# pt100.net
KiCad netlist of a schematic drawn in Altium Designer
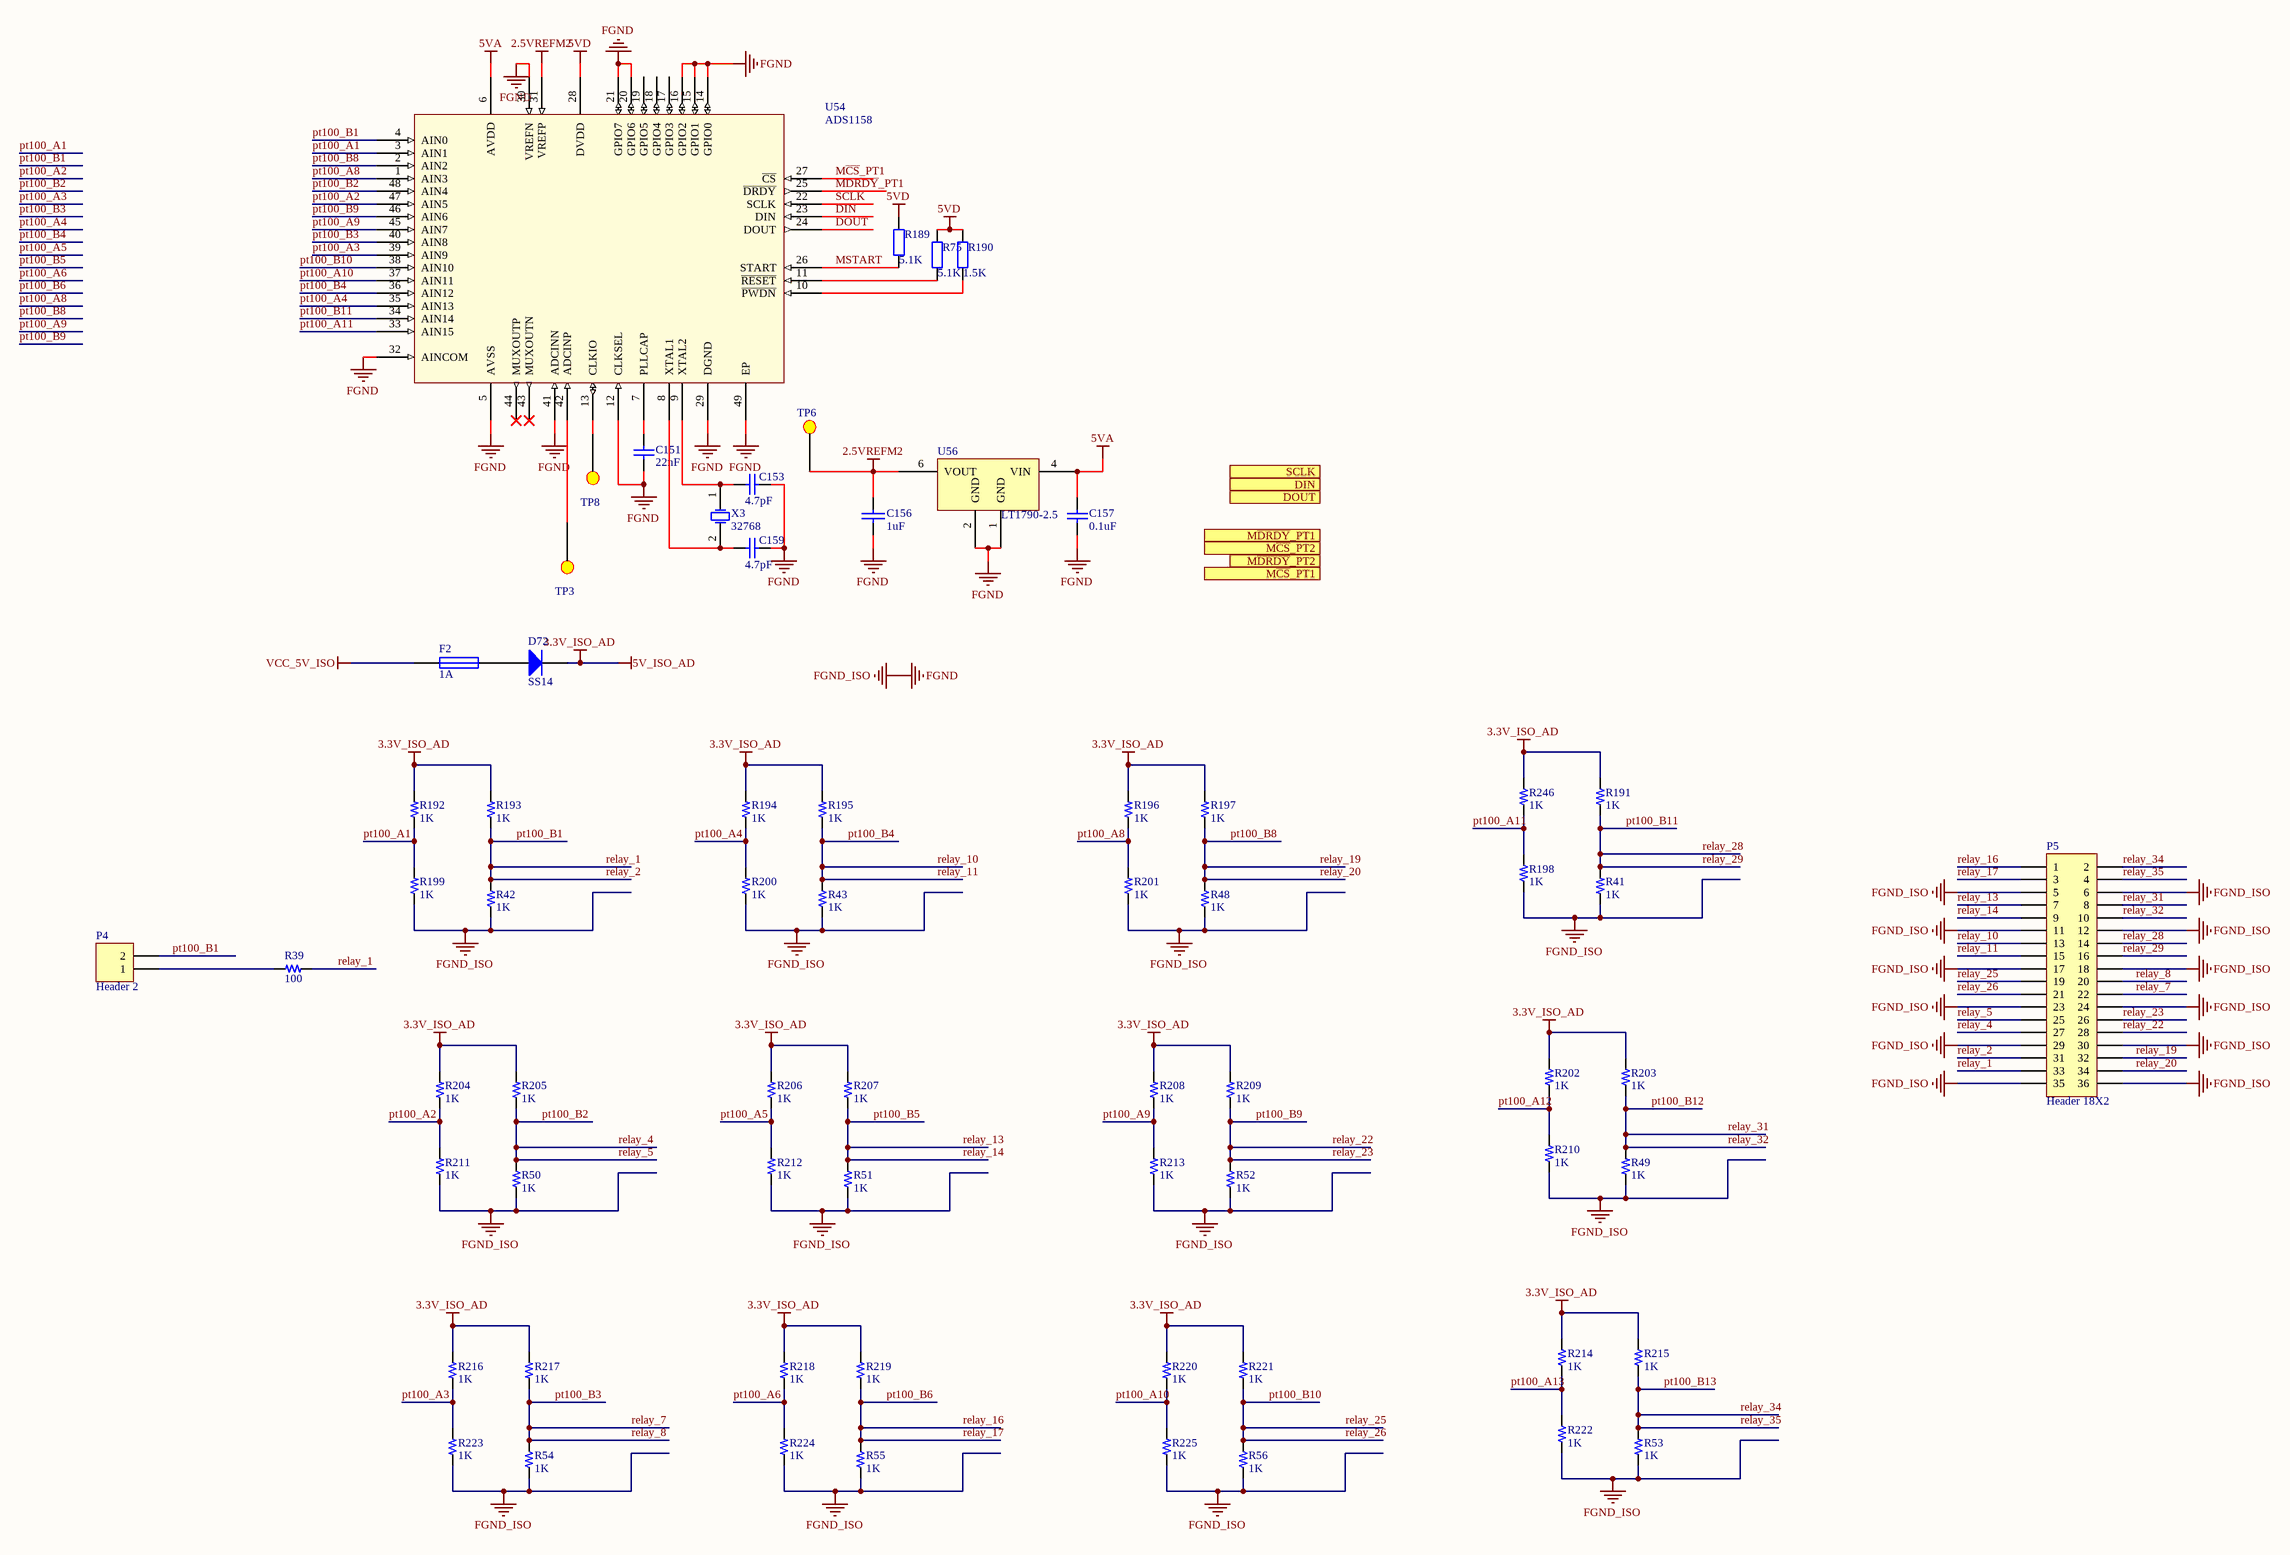
[diagram p0: pt100.SchDoc]

(export (version "E")
  (design (tool "Eeschema 10.0.6"))
  (components
    (comp (ref "C151")
      (value "22nF")
      (footprint "0805C")
      (description "Capacitor")
      (fields (field (name "PUBLISHER") "Altium Limited"))
      (libsource (lib "Miscellaneous Devices") (part "Cap"))
    )
    (comp (ref "C153")
      (value "4.7pF")
      (footprint "0603C")
      (description "Capacitor")
      (fields (field (name "PUBLISHER") "Altium Limited"))
      (libsource (lib "Miscellaneous Devices") (part "Cap"))
    )
    (comp (ref "C156")
      (value "1uF")
      (footprint "0603C")
      (description "Capacitor")
      (libsource (lib "*") (part "CAP"))
    )
    (comp (ref "C157")
      (value "0.1uF")
      (footprint "0603C")
      (description "Capacitor")
      (fields (field (name "PUBLISHER") "Altium Limited"))
      (libsource (lib "Miscellaneous Devices") (part "Cap"))
    )
    (comp (ref "C159")
      (value "4.7pF")
      (footprint "0603C")
      (description "Capacitor")
      (fields (field (name "PUBLISHER") "Altium Limited"))
      (libsource (lib "Miscellaneous Devices") (part "Cap"))
    )
    (comp (ref "D72")
      (value "SS14")
      (footprint "DO-214AC")
      (description "Default Diode")
      (fields (field (name "PUBLISHER") "Altium Limited"))
      (libsource (lib "Miscellaneous Devices") (part "Diode"))
    )
    (comp (ref "F2")
      (value "1A")
      (footprint "0805r")
      (description "Fuse")
      (fields (field (name "PUBLISHER") "Altium Limited"))
      (libsource (lib "Miscellaneous Devices") (part "Fuse 1"))
    )
    (comp (ref "P4")
      (value "Header 2")
      (footprint "HDR1X2")
      (description "Header, 2-Pin")
      (fields (field (name "PUBLISHER") "Altium Limited"))
      (libsource (lib "Miscellaneous Connectors") (part "Header 2"))
    )
    (comp (ref "P5")
      (value "Header 18X2")
      (footprint "XH2.54_2x18")
      (description "Header, 18-Pin, Dual row")
      (fields (field (name "PUBLISHER") "Altium Limited"))
      (libsource (lib "Miscellaneous Connectors") (part "Header 18X2"))
    )
    (comp (ref "R39")
      (value "100")
      (footprint "0603R")
      (description "R")
      (libsource (lib "JRJ_1") (part "R"))
    )
    (comp (ref "R41") (value "1K") (footprint "0603R") (description "R") (libsource (lib "JRJ_1") (part "R")))
    (comp (ref "R42") (value "1K") (footprint "0603R") (description "R") (libsource (lib "JRJ_1") (part "R")))
    (comp (ref "R43") (value "1K") (footprint "0603R") (description "R") (libsource (lib "JRJ_1") (part "R")))
    (comp (ref "R48") (value "1K") (footprint "0603R") (description "R") (libsource (lib "JRJ_1") (part "R")))
    (comp (ref "R49") (value "1K") (footprint "0603R") (description "R") (libsource (lib "JRJ_1") (part "R")))
    (comp (ref "R50") (value "1K") (footprint "0603R") (description "R") (libsource (lib "JRJ_1") (part "R")))
    (comp (ref "R51") (value "1K") (footprint "0603R") (description "R") (libsource (lib "JRJ_1") (part "R")))
    (comp (ref "R52") (value "1K") (footprint "0603R") (description "R") (libsource (lib "JRJ_1") (part "R")))
    (comp (ref "R53") (value "1K") (footprint "0603R") (description "R") (libsource (lib "JRJ_1") (part "R")))
    (comp (ref "R54") (value "1K") (footprint "0603R") (description "R") (libsource (lib "JRJ_1") (part "R")))
    (comp (ref "R55") (value "1K") (footprint "0603R") (description "R") (libsource (lib "JRJ_1") (part "R")))
    (comp (ref "R56") (value "1K") (footprint "0603R") (description "R") (libsource (lib "JRJ_1") (part "R")))
    (comp (ref "R75") (value "5.1K") (footprint "0603R") (libsource (lib "MQlibrary") (part "Res0805M")))
    (comp (ref "R189") (value "5.1K") (footprint "0603R") (libsource (lib "MQlibrary") (part "Res0805M")))
    (comp (ref "R190") (value "1.5K") (footprint "0603R") (libsource (lib "MQlibrary") (part "Res0805M")))
    (comp (ref "R191")
      (value "1K")
      (footprint "0603R")
      (description "R")
      (libsource (lib "JRJ_1") (part "R"))
    )
    (comp (ref "R192")
      (value "1K")
      (footprint "0603R")
      (description "R")
      (libsource (lib "JRJ_1") (part "R"))
    )
    (comp (ref "R193")
      (value "1K")
      (footprint "0603R")
      (description "R")
      (libsource (lib "JRJ_1") (part "R"))
    )
    (comp (ref "R194")
      (value "1K")
      (footprint "0603R")
      (description "R")
      (libsource (lib "JRJ_1") (part "R"))
    )
    (comp (ref "R195")
      (value "1K")
      (footprint "0603R")
      (description "R")
      (libsource (lib "JRJ_1") (part "R"))
    )
    (comp (ref "R196")
      (value "1K")
      (footprint "0603R")
      (description "R")
      (libsource (lib "JRJ_1") (part "R"))
    )
    (comp (ref "R197")
      (value "1K")
      (footprint "0603R")
      (description "R")
      (libsource (lib "JRJ_1") (part "R"))
    )
    (comp (ref "R198")
      (value "1K")
      (footprint "0603R")
      (description "R")
      (libsource (lib "JRJ_1") (part "R"))
    )
    (comp (ref "R199")
      (value "1K")
      (footprint "0603R")
      (description "R")
      (libsource (lib "JRJ_1") (part "R"))
    )
    (comp (ref "R200")
      (value "1K")
      (footprint "0603R")
      (description "R")
      (libsource (lib "JRJ_1") (part "R"))
    )
    (comp (ref "R201")
      (value "1K")
      (footprint "0603R")
      (description "R")
      (libsource (lib "JRJ_1") (part "R"))
    )
    (comp (ref "R202")
      (value "1K")
      (footprint "0603R")
      (description "R")
      (libsource (lib "JRJ_1") (part "R"))
    )
    (comp (ref "R203")
      (value "1K")
      (footprint "0603R")
      (description "R")
      (libsource (lib "JRJ_1") (part "R"))
    )
    (comp (ref "R204")
      (value "1K")
      (footprint "0603R")
      (description "R")
      (libsource (lib "JRJ_1") (part "R"))
    )
    (comp (ref "R205")
      (value "1K")
      (footprint "0603R")
      (description "R")
      (libsource (lib "JRJ_1") (part "R"))
    )
    (comp (ref "R206")
      (value "1K")
      (footprint "0603R")
      (description "R")
      (libsource (lib "JRJ_1") (part "R"))
    )
    (comp (ref "R207")
      (value "1K")
      (footprint "0603R")
      (description "R")
      (libsource (lib "JRJ_1") (part "R"))
    )
    (comp (ref "R208")
      (value "1K")
      (footprint "0603R")
      (description "R")
      (libsource (lib "JRJ_1") (part "R"))
    )
    (comp (ref "R209")
      (value "1K")
      (footprint "0603R")
      (description "R")
      (libsource (lib "JRJ_1") (part "R"))
    )
    (comp (ref "R210")
      (value "1K")
      (footprint "0603R")
      (description "R")
      (libsource (lib "JRJ_1") (part "R"))
    )
    (comp (ref "R211")
      (value "1K")
      (footprint "0603R")
      (description "R")
      (libsource (lib "JRJ_1") (part "R"))
    )
    (comp (ref "R212")
      (value "1K")
      (footprint "0603R")
      (description "R")
      (libsource (lib "JRJ_1") (part "R"))
    )
    (comp (ref "R213")
      (value "1K")
      (footprint "0603R")
      (description "R")
      (libsource (lib "JRJ_1") (part "R"))
    )
    (comp (ref "R214")
      (value "1K")
      (footprint "0603R")
      (description "R")
      (libsource (lib "JRJ_1") (part "R"))
    )
    (comp (ref "R215")
      (value "1K")
      (footprint "0603R")
      (description "R")
      (libsource (lib "JRJ_1") (part "R"))
    )
    (comp (ref "R216")
      (value "1K")
      (footprint "0603R")
      (description "R")
      (libsource (lib "JRJ_1") (part "R"))
    )
    (comp (ref "R217")
      (value "1K")
      (footprint "0603R")
      (description "R")
      (libsource (lib "JRJ_1") (part "R"))
    )
    (comp (ref "R218")
      (value "1K")
      (footprint "0603R")
      (description "R")
      (libsource (lib "JRJ_1") (part "R"))
    )
    (comp (ref "R219")
      (value "1K")
      (footprint "0603R")
      (description "R")
      (libsource (lib "JRJ_1") (part "R"))
    )
    (comp (ref "R220")
      (value "1K")
      (footprint "0603R")
      (description "R")
      (libsource (lib "JRJ_1") (part "R"))
    )
    (comp (ref "R221")
      (value "1K")
      (footprint "0603R")
      (description "R")
      (libsource (lib "JRJ_1") (part "R"))
    )
    (comp (ref "R222")
      (value "1K")
      (footprint "0603R")
      (description "R")
      (libsource (lib "JRJ_1") (part "R"))
    )
    (comp (ref "R223")
      (value "1K")
      (footprint "0603R")
      (description "R")
      (libsource (lib "JRJ_1") (part "R"))
    )
    (comp (ref "R224")
      (value "1K")
      (footprint "0603R")
      (description "R")
      (libsource (lib "JRJ_1") (part "R"))
    )
    (comp (ref "R225")
      (value "1K")
      (footprint "0603R")
      (description "R")
      (libsource (lib "JRJ_1") (part "R"))
    )
    (comp (ref "R246")
      (value "1K")
      (footprint "0603R")
      (description "R")
      (libsource (lib "JRJ_1") (part "R"))
    )
    (comp (ref "TP3")
      (value "TEST_POINT")
      (footprint "TPD")
      (libsource (lib "基带芯片OEM板_V1P0_张猛_20120921") (part "TEST_POINT"))
    )
    (comp (ref "TP6")
      (value "TEST_POINT")
      (footprint "TPD")
      (libsource (lib "基带芯片OEM板_V1P0_张猛_20120921") (part "TEST_POINT"))
    )
    (comp (ref "TP8")
      (value "TEST_POINT")
      (footprint "TPD")
      (libsource (lib "基带芯片OEM板_V1P0_张猛_20120921") (part "TEST_POINT"))
    )
    (comp (ref "U54")
      (value "ADS1158")
      (footprint "S-PVFQN-N48")
      (description "16-Channel, 16-Bit Analog-to-Digital Converter")
      (libsource (lib "Schlib") (part "ADS1158"))
    )
    (comp (ref "U56")
      (value "LT1790-2.5")
      (footprint "SOT23-6")
      (description "2.5V Micropower SOT-23  Low Dropout Reference")
      (libsource (lib "Schlib") (part "LT1790-2.5"))
    )
    (comp (ref "X3")
      (value "32768")
      (footprint "A")
      (description "Crystal Oscillator")
      (fields (field (name "PUBLISHER") "Altium Limited"))
      (libsource (lib "Miscellaneous Devices") (part "XTAL"))
    )
  )
  (nets
    (net (code "1") (name "/DIN") (class "Default")
      (node (ref "U54") (pin "23") (pinfunction "DIN_23") (pintype "input"))
    )
    (net (code "2") (name "/DOUT") (class "Default")
      (node (ref "U54") (pin "24") (pinfunction "DOUT_24") (pintype "output"))
    )
    (net (code "3") (name "/MSTART") (class "Default")
      (node (ref "R189") (pin "2") (pinfunction "2_2") (pintype "passive"))
      (node (ref "U54") (pin "26") (pinfunction "START_26") (pintype "input"))
    )
    (net (code "4") (name "/M~{CS}_PT1") (class "Default")
      (node (ref "U54") (pin "27") (pinfunction "~{CS}_27") (pintype "input"))
    )
    (net (code "6") (name "/M~{DRDY}_PT1") (class "Default")
      (node (ref "U54") (pin "25") (pinfunction "~{DRDY}_25") (pintype "output"))
    )
    (net (code "8") (name "/SCLK") (class "Default")
      (node (ref "U54") (pin "22") (pinfunction "SCLK_22") (pintype "input"))
    )
    (net (code "9") (name "/pt100_A1") (class "Default")
      (node (ref "R192") (pin "1") (pintype "passive"))
      (node (ref "R199") (pin "2") (pintype "passive"))
      (node (ref "U54") (pin "3") (pinfunction "AIN1_3") (pintype "input"))
    )
    (net (code "10") (name "/pt100_A2") (class "Default")
      (node (ref "R204") (pin "1") (pintype "passive"))
      (node (ref "R211") (pin "2") (pintype "passive"))
      (node (ref "U54") (pin "47") (pinfunction "AIN5_47") (pintype "input"))
    )
    (net (code "11") (name "/pt100_A3") (class "Default")
      (node (ref "R216") (pin "1") (pintype "passive"))
      (node (ref "R223") (pin "2") (pintype "passive"))
      (node (ref "U54") (pin "39") (pinfunction "AIN9_39") (pintype "input"))
    )
    (net (code "12") (name "/pt100_A4") (class "Default")
      (node (ref "R194") (pin "1") (pintype "passive"))
      (node (ref "R200") (pin "2") (pintype "passive"))
      (node (ref "U54") (pin "35") (pinfunction "AIN13_35") (pintype "input"))
    )
    (net (code "13") (name "/pt100_A5") (class "Default")
      (node (ref "R206") (pin "1") (pintype "passive"))
      (node (ref "R212") (pin "2") (pintype "passive"))
    )
    (net (code "14") (name "/pt100_A6") (class "Default")
      (node (ref "R218") (pin "1") (pintype "passive"))
      (node (ref "R224") (pin "2") (pintype "passive"))
    )
    (net (code "15") (name "/pt100_A8") (class "Default")
      (node (ref "R196") (pin "1") (pintype "passive"))
      (node (ref "R201") (pin "2") (pintype "passive"))
      (node (ref "U54") (pin "1") (pinfunction "AIN3_1") (pintype "input"))
    )
    (net (code "16") (name "/pt100_A9") (class "Default")
      (node (ref "R208") (pin "1") (pintype "passive"))
      (node (ref "R213") (pin "2") (pintype "passive"))
      (node (ref "U54") (pin "45") (pinfunction "AIN7_45") (pintype "input"))
    )
    (net (code "17") (name "/pt100_A10") (class "Default")
      (node (ref "R220") (pin "1") (pintype "passive"))
      (node (ref "R225") (pin "2") (pintype "passive"))
      (node (ref "U54") (pin "37") (pinfunction "AIN11_37") (pintype "input"))
    )
    (net (code "18") (name "/pt100_A11") (class "Default")
      (node (ref "R198") (pin "2") (pintype "passive"))
      (node (ref "R246") (pin "1") (pintype "passive"))
      (node (ref "U54") (pin "33") (pinfunction "AIN15_33") (pintype "input"))
    )
    (net (code "19") (name "/pt100_A12") (class "Default")
      (node (ref "R202") (pin "1") (pintype "passive"))
      (node (ref "R210") (pin "2") (pintype "passive"))
    )
    (net (code "20") (name "/pt100_A13") (class "Default")
      (node (ref "R214") (pin "1") (pintype "passive"))
      (node (ref "R222") (pin "2") (pintype "passive"))
    )
    (net (code "21") (name "/pt100_B1") (class "Default")
      (node (ref "P4") (pin "2") (pinfunction "2_2") (pintype "passive"))
      (node (ref "P5") (pin "31") (pinfunction "31_31") (pintype "passive"))
      (node (ref "P5") (pin "33") (pinfunction "33_33") (pintype "passive"))
      (node (ref "R193") (pin "1") (pintype "passive"))
      (node (ref "R39") (pin "1") (pintype "passive"))
      (node (ref "R42") (pin "2") (pintype "passive"))
      (node (ref "U54") (pin "4") (pinfunction "AIN0_4") (pintype "input"))
    )
    (net (code "22") (name "/pt100_B2") (class "Default")
      (node (ref "P5") (pin "25") (pinfunction "25_25") (pintype "passive"))
      (node (ref "P5") (pin "27") (pinfunction "27_27") (pintype "passive"))
      (node (ref "R205") (pin "1") (pintype "passive"))
      (node (ref "R50") (pin "2") (pintype "passive"))
      (node (ref "U54") (pin "48") (pinfunction "AIN4_48") (pintype "input"))
    )
    (net (code "23") (name "/pt100_B3") (class "Default")
      (node (ref "P5") (pin "20") (pinfunction "20_20") (pintype "passive"))
      (node (ref "P5") (pin "22") (pinfunction "22_22") (pintype "passive"))
      (node (ref "R217") (pin "1") (pintype "passive"))
      (node (ref "R54") (pin "2") (pintype "passive"))
      (node (ref "U54") (pin "40") (pinfunction "AIN8_40") (pintype "input"))
    )
    (net (code "24") (name "/pt100_B4") (class "Default")
      (node (ref "P5") (pin "13") (pinfunction "13_13") (pintype "passive"))
      (node (ref "P5") (pin "15") (pinfunction "15_15") (pintype "passive"))
      (node (ref "R195") (pin "1") (pintype "passive"))
      (node (ref "R43") (pin "2") (pintype "passive"))
      (node (ref "U54") (pin "36") (pinfunction "AIN12_36") (pintype "input"))
    )
    (net (code "25") (name "/pt100_B5") (class "Default")
      (node (ref "P5") (pin "7") (pinfunction "7_7") (pintype "passive"))
      (node (ref "P5") (pin "9") (pinfunction "9_9") (pintype "passive"))
      (node (ref "R207") (pin "1") (pintype "passive"))
      (node (ref "R51") (pin "2") (pintype "passive"))
    )
    (net (code "26") (name "/pt100_B6") (class "Default")
      (node (ref "P5") (pin "1") (pinfunction "1_1") (pintype "passive"))
      (node (ref "P5") (pin "3") (pinfunction "3_3") (pintype "passive"))
      (node (ref "R219") (pin "1") (pintype "passive"))
      (node (ref "R55") (pin "2") (pintype "passive"))
    )
    (net (code "27") (name "/pt100_B8") (class "Default")
      (node (ref "P5") (pin "32") (pinfunction "32_32") (pintype "passive"))
      (node (ref "P5") (pin "34") (pinfunction "34_34") (pintype "passive"))
      (node (ref "R197") (pin "1") (pintype "passive"))
      (node (ref "R48") (pin "2") (pintype "passive"))
      (node (ref "U54") (pin "2") (pinfunction "AIN2_2") (pintype "input"))
    )
    (net (code "28") (name "/pt100_B9") (class "Default")
      (node (ref "P5") (pin "26") (pinfunction "26_26") (pintype "passive"))
      (node (ref "P5") (pin "28") (pinfunction "28_28") (pintype "passive"))
      (node (ref "R209") (pin "1") (pintype "passive"))
      (node (ref "R52") (pin "2") (pintype "passive"))
      (node (ref "U54") (pin "46") (pinfunction "AIN6_46") (pintype "input"))
    )
    (net (code "29") (name "/pt100_B10") (class "Default")
      (node (ref "P5") (pin "19") (pinfunction "19_19") (pintype "passive"))
      (node (ref "P5") (pin "21") (pinfunction "21_21") (pintype "passive"))
      (node (ref "R221") (pin "1") (pintype "passive"))
      (node (ref "R56") (pin "2") (pintype "passive"))
      (node (ref "U54") (pin "38") (pinfunction "AIN10_38") (pintype "input"))
    )
    (net (code "30") (name "/pt100_B11") (class "Default")
      (node (ref "P5") (pin "14") (pinfunction "14_14") (pintype "passive"))
      (node (ref "P5") (pin "16") (pinfunction "16_16") (pintype "passive"))
      (node (ref "R191") (pin "1") (pintype "passive"))
      (node (ref "R41") (pin "2") (pintype "passive"))
      (node (ref "U54") (pin "34") (pinfunction "AIN14_34") (pintype "input"))
    )
    (net (code "31") (name "/pt100_B12") (class "Default")
      (node (ref "P5") (pin "10") (pinfunction "10_10") (pintype "passive"))
      (node (ref "P5") (pin "8") (pinfunction "8_8") (pintype "passive"))
      (node (ref "R203") (pin "1") (pintype "passive"))
      (node (ref "R49") (pin "2") (pintype "passive"))
    )
    (net (code "32") (name "/pt100_B13") (class "Default")
      (node (ref "P5") (pin "2") (pinfunction "2_2") (pintype "passive"))
      (node (ref "P5") (pin "4") (pinfunction "4_4") (pintype "passive"))
      (node (ref "R215") (pin "1") (pintype "passive"))
      (node (ref "R53") (pin "2") (pintype "passive"))
    )
    (net (code "33") (name "2.5VREFM2") (class "Default")
      (node (ref "C156") (pin "1") (pinfunction "1_1") (pintype "passive"))
      (node (ref "TP6") (pin "1") (pinfunction "1_1") (pintype "passive"))
      (node (ref "U54") (pin "31") (pinfunction "VREFP_31") (pintype "input"))
      (node (ref "U56") (pin "6") (pinfunction "VOUT_6") (pintype "power_in"))
    )
    (net (code "34") (name "3.3V_ISO_AD") (class "Default")
      (node (ref "D72") (pin "2") (pinfunction "K_2") (pintype "passive"))
      (node (ref "R191") (pin "2") (pintype "passive"))
      (node (ref "R192") (pin "2") (pintype "passive"))
      (node (ref "R193") (pin "2") (pintype "passive"))
      (node (ref "R194") (pin "2") (pintype "passive"))
      (node (ref "R195") (pin "2") (pintype "passive"))
      (node (ref "R196") (pin "2") (pintype "passive"))
      (node (ref "R197") (pin "2") (pintype "passive"))
      (node (ref "R202") (pin "2") (pintype "passive"))
      (node (ref "R203") (pin "2") (pintype "passive"))
      (node (ref "R204") (pin "2") (pintype "passive"))
      (node (ref "R205") (pin "2") (pintype "passive"))
      (node (ref "R206") (pin "2") (pintype "passive"))
      (node (ref "R207") (pin "2") (pintype "passive"))
      (node (ref "R208") (pin "2") (pintype "passive"))
      (node (ref "R209") (pin "2") (pintype "passive"))
      (node (ref "R214") (pin "2") (pintype "passive"))
      (node (ref "R215") (pin "2") (pintype "passive"))
      (node (ref "R216") (pin "2") (pintype "passive"))
      (node (ref "R217") (pin "2") (pintype "passive"))
      (node (ref "R218") (pin "2") (pintype "passive"))
      (node (ref "R219") (pin "2") (pintype "passive"))
      (node (ref "R220") (pin "2") (pintype "passive"))
      (node (ref "R221") (pin "2") (pintype "passive"))
      (node (ref "R246") (pin "2") (pintype "passive"))
    )
    (net (code "35") (name "5VA") (class "Default")
      (node (ref "C157") (pin "2") (pinfunction "2_2") (pintype "passive"))
      (node (ref "U54") (pin "6") (pinfunction "AVDD_6") (pintype "passive"))
      (node (ref "U56") (pin "4") (pinfunction "VIN_4") (pintype "power_in"))
    )
    (net (code "36") (name "5VD") (class "Default")
      (node (ref "R189") (pin "1") (pinfunction "1_1") (pintype "passive"))
      (node (ref "R190") (pin "1") (pinfunction "1_1") (pintype "passive"))
      (node (ref "R75") (pin "1") (pinfunction "1_1") (pintype "passive"))
      (node (ref "U54") (pin "28") (pinfunction "DVDD_28") (pintype "power_in"))
    )
    (net (code "37") (name "FGND") (class "Default")
      (node (ref "C151") (pin "2") (pinfunction "2_2") (pintype "passive"))
      (node (ref "C153") (pin "2") (pinfunction "2_2") (pintype "passive"))
      (node (ref "C156") (pin "2") (pinfunction "2_2") (pintype "passive"))
      (node (ref "C157") (pin "1") (pinfunction "1_1") (pintype "passive"))
      (node (ref "C159") (pin "2") (pinfunction "2_2") (pintype "passive"))
      (node (ref "P5") (pin "11") (pinfunction "11_11") (pintype "passive"))
      (node (ref "P5") (pin "12") (pinfunction "12_12") (pintype "passive"))
      (node (ref "P5") (pin "17") (pinfunction "17_17") (pintype "passive"))
      (node (ref "P5") (pin "18") (pinfunction "18_18") (pintype "passive"))
      (node (ref "P5") (pin "23") (pinfunction "23_23") (pintype "passive"))
      (node (ref "P5") (pin "24") (pinfunction "24_24") (pintype "passive"))
      (node (ref "P5") (pin "29") (pinfunction "29_29") (pintype "passive"))
      (node (ref "P5") (pin "30") (pinfunction "30_30") (pintype "passive"))
      (node (ref "P5") (pin "35") (pinfunction "35_35") (pintype "passive"))
      (node (ref "P5") (pin "36") (pinfunction "36_36") (pintype "passive"))
      (node (ref "P5") (pin "5") (pinfunction "5_5") (pintype "passive"))
      (node (ref "P5") (pin "6") (pinfunction "6_6") (pintype "passive"))
      (node (ref "R198") (pin "1") (pintype "passive"))
      (node (ref "R199") (pin "1") (pintype "passive"))
      (node (ref "R200") (pin "1") (pintype "passive"))
      (node (ref "R201") (pin "1") (pintype "passive"))
      (node (ref "R210") (pin "1") (pintype "passive"))
      (node (ref "R211") (pin "1") (pintype "passive"))
      (node (ref "R212") (pin "1") (pintype "passive"))
      (node (ref "R213") (pin "1") (pintype "passive"))
      (node (ref "R222") (pin "1") (pintype "passive"))
      (node (ref "R223") (pin "1") (pintype "passive"))
      (node (ref "R224") (pin "1") (pintype "passive"))
      (node (ref "R225") (pin "1") (pintype "passive"))
      (node (ref "R41") (pin "1") (pintype "passive"))
      (node (ref "R42") (pin "1") (pintype "passive"))
      (node (ref "R43") (pin "1") (pintype "passive"))
      (node (ref "R48") (pin "1") (pintype "passive"))
      (node (ref "R49") (pin "1") (pintype "passive"))
      (node (ref "R50") (pin "1") (pintype "passive"))
      (node (ref "R51") (pin "1") (pintype "passive"))
      (node (ref "R52") (pin "1") (pintype "passive"))
      (node (ref "R53") (pin "1") (pintype "passive"))
      (node (ref "R54") (pin "1") (pintype "passive"))
      (node (ref "R55") (pin "1") (pintype "passive"))
      (node (ref "R56") (pin "1") (pintype "passive"))
      (node (ref "U54") (pin "12") (pinfunction "CLKSEL_12") (pintype "input"))
      (node (ref "U54") (pin "14") (pinfunction "GPIO0_14") (pintype "bidirectional"))
      (node (ref "U54") (pin "15") (pinfunction "GPIO1_15") (pintype "bidirectional"))
      (node (ref "U54") (pin "16") (pinfunction "GPIO2_16") (pintype "bidirectional"))
      (node (ref "U54") (pin "20") (pinfunction "GPIO6_20") (pintype "bidirectional"))
      (node (ref "U54") (pin "21") (pinfunction "GPIO7_21") (pintype "bidirectional"))
      (node (ref "U54") (pin "29") (pinfunction "DGND_29") (pintype "power_in"))
      (node (ref "U54") (pin "30") (pinfunction "VREFN_30") (pintype "input"))
      (node (ref "U54") (pin "32") (pinfunction "AINCOM_32") (pintype "input"))
      (node (ref "U54") (pin "41") (pinfunction "ADCINN_41") (pintype "input"))
      (node (ref "U54") (pin "49") (pinfunction "EP_49") (pintype "passive"))
      (node (ref "U54") (pin "5") (pinfunction "AVSS_5") (pintype "power_in"))
      (node (ref "U56") (pin "1") (pinfunction "GND_1") (pintype "power_in"))
      (node (ref "U56") (pin "2") (pinfunction "GND_2") (pintype "power_in"))
    )
    (net (code "38") (name "Net-(D72-A)") (class "Default")
      (node (ref "D72") (pin "1") (pinfunction "A_1") (pintype "passive"))
      (node (ref "F2") (pin "2") (pinfunction "2_2") (pintype "passive"))
    )
    (net (code "39") (name "Net-(P4-Pad1)") (class "Default")
      (node (ref "P4") (pin "1") (pinfunction "1_1") (pintype "passive"))
      (node (ref "R39") (pin "2") (pintype "passive"))
    )
    (net (code "40") (name "Net-(U54-ADCINP)") (class "Default")
      (node (ref "TP3") (pin "1") (pinfunction "1_1") (pintype "passive"))
      (node (ref "U54") (pin "42") (pinfunction "ADCINP_42") (pintype "input"))
    )
    (net (code "41") (name "Net-(U54-CLKIO)") (class "Default")
      (node (ref "TP8") (pin "1") (pinfunction "1_1") (pintype "passive"))
      (node (ref "U54") (pin "13") (pinfunction "CLKIO_13") (pintype "bidirectional"))
    )
    (net (code "42") (name "Net-(U54-PLLCAP)") (class "Default")
      (node (ref "C151") (pin "1") (pinfunction "1_1") (pintype "passive"))
      (node (ref "U54") (pin "7") (pinfunction "PLLCAP_7") (pintype "power_in"))
    )
    (net (code "43") (name "Net-(U54-XTAL1)") (class "Default")
      (node (ref "C159") (pin "1") (pinfunction "1_1") (pintype "passive"))
      (node (ref "U54") (pin "8") (pinfunction "XTAL1_8") (pintype "passive"))
      (node (ref "X3") (pin "2") (pinfunction "OSC2_2") (pintype "passive"))
    )
    (net (code "44") (name "Net-(U54-XTAL2)") (class "Default")
      (node (ref "C153") (pin "1") (pinfunction "1_1") (pintype "passive"))
      (node (ref "U54") (pin "9") (pinfunction "XTAL2_9") (pintype "passive"))
      (node (ref "X3") (pin "1") (pinfunction "OSC1_1") (pintype "passive"))
    )
    (net (code "45") (name "Net-(U54-~{PWDN})") (class "Default")
      (node (ref "R190") (pin "2") (pinfunction "2_2") (pintype "passive"))
      (node (ref "U54") (pin "10") (pinfunction "~{PWDN}_10") (pintype "input"))
    )
    (net (code "46") (name "Net-(U54-~{RESET})") (class "Default")
      (node (ref "R75") (pin "2") (pinfunction "2_2") (pintype "passive"))
      (node (ref "U54") (pin "11") (pinfunction "~{RESET}_11") (pintype "input"))
    )
    (net (code "47") (name "VCC_5V_ISO") (class "Default")
      (node (ref "F2") (pin "1") (pinfunction "1_1") (pintype "passive"))
    )
    (net (code "48") (name "unconnected-(U54-GPIO3-Pad17)") (class "Default")
      (node (ref "U54") (pin "17") (pinfunction "GPIO3_17") (pintype "bidirectional"))
    )
    (net (code "49") (name "unconnected-(U54-GPIO4-Pad18)") (class "Default")
      (node (ref "U54") (pin "18") (pinfunction "GPIO4_18") (pintype "bidirectional"))
    )
    (net (code "50") (name "unconnected-(U54-GPIO5-Pad19)") (class "Default")
      (node (ref "U54") (pin "19") (pinfunction "GPIO5_19") (pintype "bidirectional"))
    )
    (net (code "51") (name "unconnected-(U54-MUXOUTN-Pad43)") (class "Default")
      (node (ref "U54") (pin "43") (pinfunction "MUXOUTN_43") (pintype "output+no_connect"))
    )
    (net (code "52") (name "unconnected-(U54-MUXOUTP-Pad44)") (class "Default")
      (node (ref "U54") (pin "44") (pinfunction "MUXOUTP_44") (pintype "output+no_connect"))
    )
    (net (code "53") (name "unconnected-(U56-DNC-Pad3)") (class "Default")
      (node (ref "U56") (pin "3") (pinfunction "DNC_3") (pintype "passive"))
    )
    (net (code "54") (name "unconnected-(U56-DNC-Pad5)") (class "Default")
      (node (ref "U56") (pin "5") (pinfunction "DNC_5") (pintype "passive"))
    )
  )
)
